# LT1301_1r.net
KiCad netlist of a schematic drawn in EAGLE
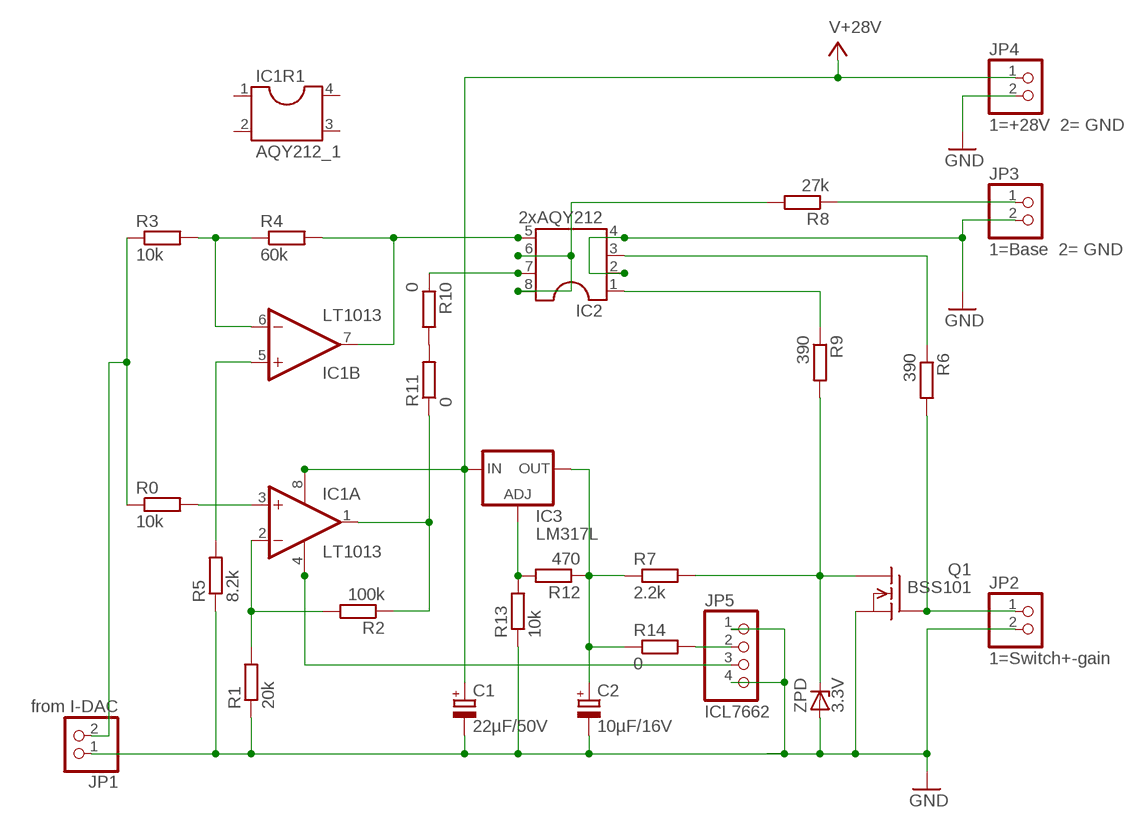
[diagram p0: schematic, sheet 1]

(export (version "E")
  (design (tool "Eeschema 10.0.6"))
  (components
    (comp (ref "C1")
      (value "22µF/50V")
      (footprint "eagle-import:E5-10,5")
      (libsource (lib "eagle-import") (part "CPOL-EUE5-10.5"))
    )
    (comp (ref "C2")
      (value "10µF/16V")
      (footprint "eagle-import:B45181B")
      (libsource (lib "eagle-import") (part "resistor_348_CPOL-EUB45181B"))
    )
    (comp (ref "IC1")
      (value "LT1013")
      (footprint "eagle-import:DIL08")
      (libsource (lib "eagle-import") (part "LF412N"))
    )
    (comp (ref "IC1R1")
      (value "AQY212_1")
      (footprint "eagle-import:SOCKET-04")
      (libsource (lib "eagle-import") (part "DIL4S"))
    )
    (comp (ref "IC2")
      (value "2xAQY212")
      (footprint "eagle-import:SOCKET-08")
      (libsource (lib "eagle-import") (part "DIL8S"))
    )
    (comp (ref "IC3")
      (value "LM317L")
      (footprint "eagle-import:317L")
      (libsource (lib "eagle-import") (part "LM317L"))
    )
    (comp (ref "JP1")
      (value "from I-DAC")
      (footprint "eagle-import:1X02")
      (libsource (lib "eagle-import") (part "PINHD-1X2"))
    )
    (comp (ref "JP2")
      (value "1=Switch+-gain")
      (footprint "eagle-import:1X02")
      (libsource (lib "eagle-import") (part "PINHD-1X2"))
    )
    (comp (ref "JP3")
      (value "1=Base 2= GND")
      (footprint "eagle-import:1X02")
      (libsource (lib "eagle-import") (part "PINHD-1X2"))
    )
    (comp (ref "JP4")
      (value "1=+28V 2= GND")
      (footprint "eagle-import:1X02")
      (libsource (lib "eagle-import") (part "PINHD-1X2"))
    )
    (comp (ref "JP5")
      (value "ICL7662")
      (footprint "eagle-import:1X04")
      (libsource (lib "eagle-import") (part "PINHD-1X4"))
    )
    (comp (ref "Q1")
      (value "BSS101")
      (footprint "eagle-import:TO92")
      (libsource (lib "eagle-import") (part "BSS101"))
    )
    (comp (ref "R0")
      (value "10k")
      (footprint "eagle-import:0207_7")
      (libsource (lib "eagle-import") (part "R-EU_0207/7"))
    )
    (comp (ref "R1")
      (value "20k")
      (footprint "eagle-import:0207_7")
      (libsource (lib "eagle-import") (part "R-EU_0207/7"))
    )
    (comp (ref "R2")
      (value "100k")
      (footprint "eagle-import:0207_7")
      (libsource (lib "eagle-import") (part "R-EU_0207/7"))
    )
    (comp (ref "R3")
      (value "10k")
      (footprint "eagle-import:0207_7")
      (libsource (lib "eagle-import") (part "R-EU_0207/7"))
    )
    (comp (ref "R4")
      (value "60k")
      (footprint "eagle-import:0207_7")
      (libsource (lib "eagle-import") (part "R-EU_0207/7"))
    )
    (comp (ref "R5")
      (value "8.2k")
      (footprint "eagle-import:0207_7")
      (libsource (lib "eagle-import") (part "R-EU_0207/7"))
    )
    (comp (ref "R6")
      (value "390")
      (footprint "eagle-import:0207_7")
      (libsource (lib "eagle-import") (part "R-EU_0207/7"))
    )
    (comp (ref "R7")
      (value "2.2k")
      (footprint "eagle-import:0207_7")
      (libsource (lib "eagle-import") (part "R-EU_0207/7"))
    )
    (comp (ref "R8")
      (value "27k")
      (footprint "eagle-import:0207_7")
      (libsource (lib "eagle-import") (part "R-EU_0207/7"))
    )
    (comp (ref "R9")
      (value "390")
      (footprint "eagle-import:0207_7")
      (libsource (lib "eagle-import") (part "R-EU_0207/7"))
    )
    (comp (ref "R10")
      (value "0")
      (footprint "eagle-import:0207_7")
      (libsource (lib "eagle-import") (part "R-EU_0207/7"))
    )
    (comp (ref "R11")
      (value "0")
      (footprint "eagle-import:0207_7")
      (libsource (lib "eagle-import") (part "R-EU_0207/7"))
    )
    (comp (ref "R12")
      (value "470")
      (footprint "eagle-import:0207_7")
      (libsource (lib "eagle-import") (part "R-EU_0207/7"))
    )
    (comp (ref "R13")
      (value "10k")
      (footprint "eagle-import:0207_7")
      (libsource (lib "eagle-import") (part "R-EU_0207/7"))
    )
    (comp (ref "R14")
      (value "0")
      (footprint "eagle-import:0207_7")
      (libsource (lib "eagle-import") (part "R-EU_0207/7"))
    )
    (comp (ref "ZPD")
      (value "3.3V")
      (footprint "eagle-import:ZDIO-7.5")
      (libsource (lib "eagle-import") (part "ZENER-DIODEZD-7.5"))
    )
  )
  (nets
    (net (code "1") (name "GND") (class "Default")
      (node (ref "C1") (pin "-") (pinfunction "-_-") (pintype "passive"))
      (node (ref "C2") (pin "-") (pinfunction "-_-") (pintype "passive"))
      (node (ref "IC2") (pin "2") (pinfunction "2_2") (pintype "passive"))
      (node (ref "IC2") (pin "4") (pinfunction "4_4") (pintype "passive"))
      (node (ref "JP1") (pin "1") (pinfunction "1_1") (pintype "passive"))
      (node (ref "JP2") (pin "2") (pinfunction "2_2") (pintype "passive"))
      (node (ref "JP3") (pin "2") (pinfunction "2_2") (pintype "passive"))
      (node (ref "JP4") (pin "2") (pinfunction "2_2") (pintype "passive"))
      (node (ref "JP5") (pin "1") (pinfunction "1_1") (pintype "passive"))
      (node (ref "JP5") (pin "4") (pinfunction "4_4") (pintype "passive"))
      (node (ref "Q1") (pin "1") (pinfunction "S_1") (pintype "passive"))
      (node (ref "R1") (pin "1") (pinfunction "1_1") (pintype "passive"))
      (node (ref "R13") (pin "1") (pinfunction "1_1") (pintype "passive"))
      (node (ref "R5") (pin "1") (pinfunction "1_1") (pintype "passive"))
      (node (ref "ZPD") (pin "A") (pinfunction "A_A") (pintype "passive"))
    )
    (net (code "2") (name "Net-(IC1A-+IN)") (class "Default")
      (node (ref "IC1") (pin "3") (pinfunction "+IN_3") (pintype "input"))
      (node (ref "R0") (pin "2") (pinfunction "2_2") (pintype "passive"))
    )
    (net (code "3") (name "Net-(IC1A--IN)") (class "Default")
      (node (ref "IC1") (pin "2") (pinfunction "-IN_2") (pintype "input"))
      (node (ref "R1") (pin "2") (pinfunction "2_2") (pintype "passive"))
      (node (ref "R2") (pin "2") (pinfunction "2_2") (pintype "passive"))
    )
    (net (code "4") (name "Net-(IC1A-OUT)") (class "Default")
      (node (ref "IC1") (pin "1") (pinfunction "OUT_1") (pintype "output"))
      (node (ref "R11") (pin "1") (pinfunction "1_1") (pintype "passive"))
      (node (ref "R2") (pin "1") (pinfunction "1_1") (pintype "passive"))
    )
    (net (code "5") (name "Net-(IC1B-+IN)") (class "Default")
      (node (ref "IC1") (pin "5") (pinfunction "+IN_5") (pintype "input"))
      (node (ref "R5") (pin "2") (pinfunction "2_2") (pintype "passive"))
    )
    (net (code "6") (name "Net-(IC1B--IN)") (class "Default")
      (node (ref "IC1") (pin "6") (pinfunction "-IN_6") (pintype "input"))
      (node (ref "R3") (pin "2") (pinfunction "2_2") (pintype "passive"))
      (node (ref "R4") (pin "1") (pinfunction "1_1") (pintype "passive"))
    )
    (net (code "7") (name "Net-(IC1B-OUT)") (class "Default")
      (node (ref "IC1") (pin "7") (pinfunction "OUT_7") (pintype "output"))
      (node (ref "IC2") (pin "5") (pinfunction "5_5") (pintype "passive"))
      (node (ref "R4") (pin "2") (pinfunction "2_2") (pintype "passive"))
    )
    (net (code "8") (name "Net-(IC1C-V-)") (class "Default")
      (node (ref "IC1") (pin "4") (pinfunction "V-_4") (pintype "power_in"))
      (node (ref "JP5") (pin "3") (pinfunction "3_3") (pintype "passive"))
    )
    (net (code "9") (name "Net-(IC2-Pad1)") (class "Default")
      (node (ref "IC2") (pin "1") (pinfunction "1_1") (pintype "passive"))
      (node (ref "R9") (pin "1") (pinfunction "1_1") (pintype "passive"))
    )
    (net (code "10") (name "Net-(IC2-Pad3)") (class "Default")
      (node (ref "IC2") (pin "3") (pinfunction "3_3") (pintype "passive"))
      (node (ref "R6") (pin "1") (pinfunction "1_1") (pintype "passive"))
    )
    (net (code "11") (name "Net-(IC2-Pad6)") (class "Default")
      (node (ref "IC2") (pin "6") (pinfunction "6_6") (pintype "passive"))
      (node (ref "IC2") (pin "8") (pinfunction "8_8") (pintype "passive"))
      (node (ref "R8") (pin "2") (pinfunction "2_2") (pintype "passive"))
    )
    (net (code "12") (name "Net-(IC2-Pad7)") (class "Default")
      (node (ref "IC2") (pin "7") (pinfunction "7_7") (pintype "passive"))
      (node (ref "R10") (pin "1") (pinfunction "1_1") (pintype "passive"))
    )
    (net (code "13") (name "Net-(IC3-ADJ)") (class "Default")
      (node (ref "IC3") (pin "1") (pinfunction "ADJ_1") (pintype "input"))
      (node (ref "R12") (pin "2") (pinfunction "2_2") (pintype "passive"))
      (node (ref "R13") (pin "2") (pinfunction "2_2") (pintype "passive"))
    )
    (net (code "14") (name "Net-(IC3-OUT)") (class "Default")
      (node (ref "C2") (pin "+") (pinfunction "+_+") (pintype "passive"))
      (node (ref "IC3") (pin "2") (pinfunction "OUT_2") (pintype "passive"))
      (node (ref "R12") (pin "1") (pinfunction "1_1") (pintype "passive"))
      (node (ref "R14") (pin "1") (pinfunction "1_1") (pintype "passive"))
      (node (ref "R7") (pin "1") (pinfunction "1_1") (pintype "passive"))
    )
    (net (code "15") (name "Net-(JP1-Pad2)") (class "Default")
      (node (ref "JP1") (pin "2") (pinfunction "2_2") (pintype "passive"))
      (node (ref "R0") (pin "1") (pinfunction "1_1") (pintype "passive"))
      (node (ref "R3") (pin "1") (pinfunction "1_1") (pintype "passive"))
    )
    (net (code "16") (name "Net-(JP3-Pad1)") (class "Default")
      (node (ref "JP3") (pin "1") (pinfunction "1_1") (pintype "passive"))
      (node (ref "R8") (pin "1") (pinfunction "1_1") (pintype "passive"))
    )
    (net (code "17") (name "Net-(JP5-Pad2)") (class "Default")
      (node (ref "JP5") (pin "2") (pinfunction "2_2") (pintype "passive"))
      (node (ref "R14") (pin "2") (pinfunction "2_2") (pintype "passive"))
    )
    (net (code "18") (name "Net-(Q1-D)") (class "Default")
      (node (ref "Q1") (pin "3") (pinfunction "D_3") (pintype "passive"))
      (node (ref "R7") (pin "2") (pinfunction "2_2") (pintype "passive"))
      (node (ref "R9") (pin "2") (pinfunction "2_2") (pintype "passive"))
      (node (ref "ZPD") (pin "C") (pinfunction "C_C") (pintype "passive"))
    )
    (net (code "19") (name "Net-(Q1-G)") (class "Default")
      (node (ref "JP2") (pin "1") (pinfunction "1_1") (pintype "passive"))
      (node (ref "Q1") (pin "2") (pinfunction "G_2") (pintype "passive"))
      (node (ref "R6") (pin "2") (pinfunction "2_2") (pintype "passive"))
    )
    (net (code "20") (name "Net-(R10-Pad2)") (class "Default")
      (node (ref "R10") (pin "2") (pinfunction "2_2") (pintype "passive"))
      (node (ref "R11") (pin "2") (pinfunction "2_2") (pintype "passive"))
    )
    (net (code "21") (name "V+28V") (class "Default")
      (node (ref "C1") (pin "+") (pinfunction "+_+") (pintype "passive"))
      (node (ref "IC1") (pin "8") (pinfunction "V+_8") (pintype "power_in"))
      (node (ref "IC3") (pin "3") (pinfunction "IN_3") (pintype "input"))
      (node (ref "JP4") (pin "1") (pinfunction "1_1") (pintype "passive"))
    )
    (net (code "22") (name "unconnected-(IC1R1-Pad1)") (class "Default")
      (node (ref "IC1R1") (pin "1") (pinfunction "1_1") (pintype "passive"))
    )
    (net (code "23") (name "unconnected-(IC1R1-Pad2)") (class "Default")
      (node (ref "IC1R1") (pin "2") (pinfunction "2_2") (pintype "passive"))
    )
    (net (code "24") (name "unconnected-(IC1R1-Pad3)") (class "Default")
      (node (ref "IC1R1") (pin "3") (pinfunction "3_3") (pintype "passive"))
    )
    (net (code "25") (name "unconnected-(IC1R1-Pad4)") (class "Default")
      (node (ref "IC1R1") (pin "4") (pinfunction "4_4") (pintype "passive"))
    )
  )
)
